# relay.net
KiCad netlist of a schematic drawn in Altium Designer
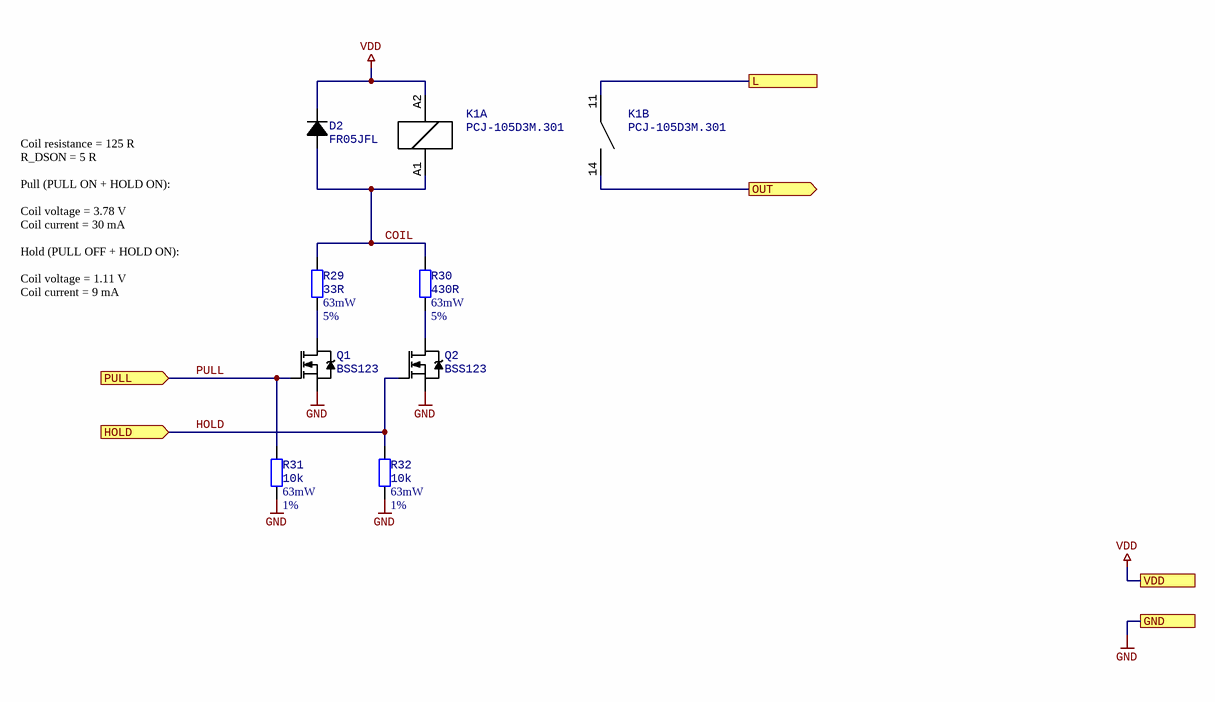
[diagram p0: relay.SchDoc]

(export (version "E")
  (design (tool "Eeschema 10.0.6"))
  (components
    (comp (ref "D2")
      (value "FR05JFL")
      (footprint "SOD323")
      (description "FAST RECOVERY SURFACE MOUNT GLASS PASSIVATED RECTIFIER")
      (fields (field (name "MANUFACTURER") "DC Components"))
      (libsource (lib "diode") (part "FR05xFL"))
    )
    (comp (ref "K1")
      (value "PCJ-105D3M.301")
      (footprint "1721081-2")
      (description "Miniature PCB Relay PCJ")
      (fields (field (name "MANUFACTURER") "TE Connectivity"))
      (libsource (lib "relay") (part "PCJ-1xxD3M.301"))
    )
    (comp (ref "Q1")
      (value "BSS123")
      (footprint "sot23-3l")
      (description "N-Channel Logic Level Enhancement Mode Field Effect Transistor")
      (libsource (lib "transistor") (part "BSS123"))
    )
    (comp (ref "Q2")
      (value "BSS123")
      (footprint "sot23-3l")
      (description "N-Channel Logic Level Enhancement Mode Field Effect Transistor")
      (libsource (lib "transistor") (part "BSS123"))
    )
    (comp (ref "R29")
      (value "33R")
      (footprint "RES0603")
      (description "Generic resistor symbol")
      (fields (field (name "POWER") "63mW") (field (name "TOLERANCE") "5%"))
      (libsource (lib "resistor") (part "Resistor"))
    )
    (comp (ref "R30")
      (value "430R")
      (footprint "RES0603")
      (description "Generic resistor symbol")
      (fields (field (name "POWER") "63mW") (field (name "TOLERANCE") "5%"))
      (libsource (lib "resistor") (part "Resistor"))
    )
    (comp (ref "R31")
      (value "10k")
      (footprint "RES0603")
      (description "Generic resistor symbol")
      (fields (field (name "POWER") "63mW") (field (name "TOLERANCE") "1%"))
      (libsource (lib "resistor") (part "Resistor"))
    )
    (comp (ref "R32")
      (value "10k")
      (footprint "RES0603")
      (description "Generic resistor symbol")
      (fields (field (name "POWER") "63mW") (field (name "TOLERANCE") "1%"))
      (libsource (lib "resistor") (part "Resistor"))
    )
  )
  (nets
    (net (code "1") (name "/COIL") (class "Default")
      (node (ref "D2") (pin "2") (pinfunction "A_2") (pintype "passive"))
      (node (ref "K1") (pin "A1") (pinfunction "A1_A1") (pintype "passive"))
      (node (ref "R29") (pin "1") (pinfunction "1_1") (pintype "passive"))
      (node (ref "R30") (pin "1") (pinfunction "1_1") (pintype "passive"))
    )
    (net (code "2") (name "/HOLD") (class "Default")
      (node (ref "Q2") (pin "1") (pinfunction "G_1") (pintype "passive"))
      (node (ref "R32") (pin "1") (pinfunction "1_1") (pintype "passive"))
    )
    (net (code "3") (name "/L") (class "Default")
      (node (ref "K1") (pin "11") (pinfunction "11_11") (pintype "passive"))
    )
    (net (code "4") (name "/OUT") (class "Default")
      (node (ref "K1") (pin "14") (pinfunction "14_14") (pintype "passive"))
    )
    (net (code "5") (name "/PULL") (class "Default")
      (node (ref "Q1") (pin "1") (pinfunction "G_1") (pintype "passive"))
      (node (ref "R31") (pin "1") (pinfunction "1_1") (pintype "passive"))
    )
    (net (code "6") (name "GND") (class "Default")
      (node (ref "Q1") (pin "2") (pinfunction "S_2") (pintype "passive"))
      (node (ref "Q2") (pin "2") (pinfunction "S_2") (pintype "passive"))
      (node (ref "R31") (pin "2") (pinfunction "2_2") (pintype "passive"))
      (node (ref "R32") (pin "2") (pinfunction "2_2") (pintype "passive"))
    )
    (net (code "7") (name "Net-(Q1-D)") (class "Default")
      (node (ref "Q1") (pin "3") (pinfunction "D_3") (pintype "passive"))
      (node (ref "R29") (pin "2") (pinfunction "2_2") (pintype "passive"))
    )
    (net (code "8") (name "Net-(Q2-D)") (class "Default")
      (node (ref "Q2") (pin "3") (pinfunction "D_3") (pintype "passive"))
      (node (ref "R30") (pin "2") (pinfunction "2_2") (pintype "passive"))
    )
    (net (code "9") (name "VDD") (class "Default")
      (node (ref "D2") (pin "1") (pinfunction "K_1") (pintype "passive"))
      (node (ref "K1") (pin "A2") (pinfunction "A2_A2") (pintype "passive"))
    )
  )
)
